# BRG_Daughter_Single.net
KiCad netlist of a schematic drawn in Altium Designer
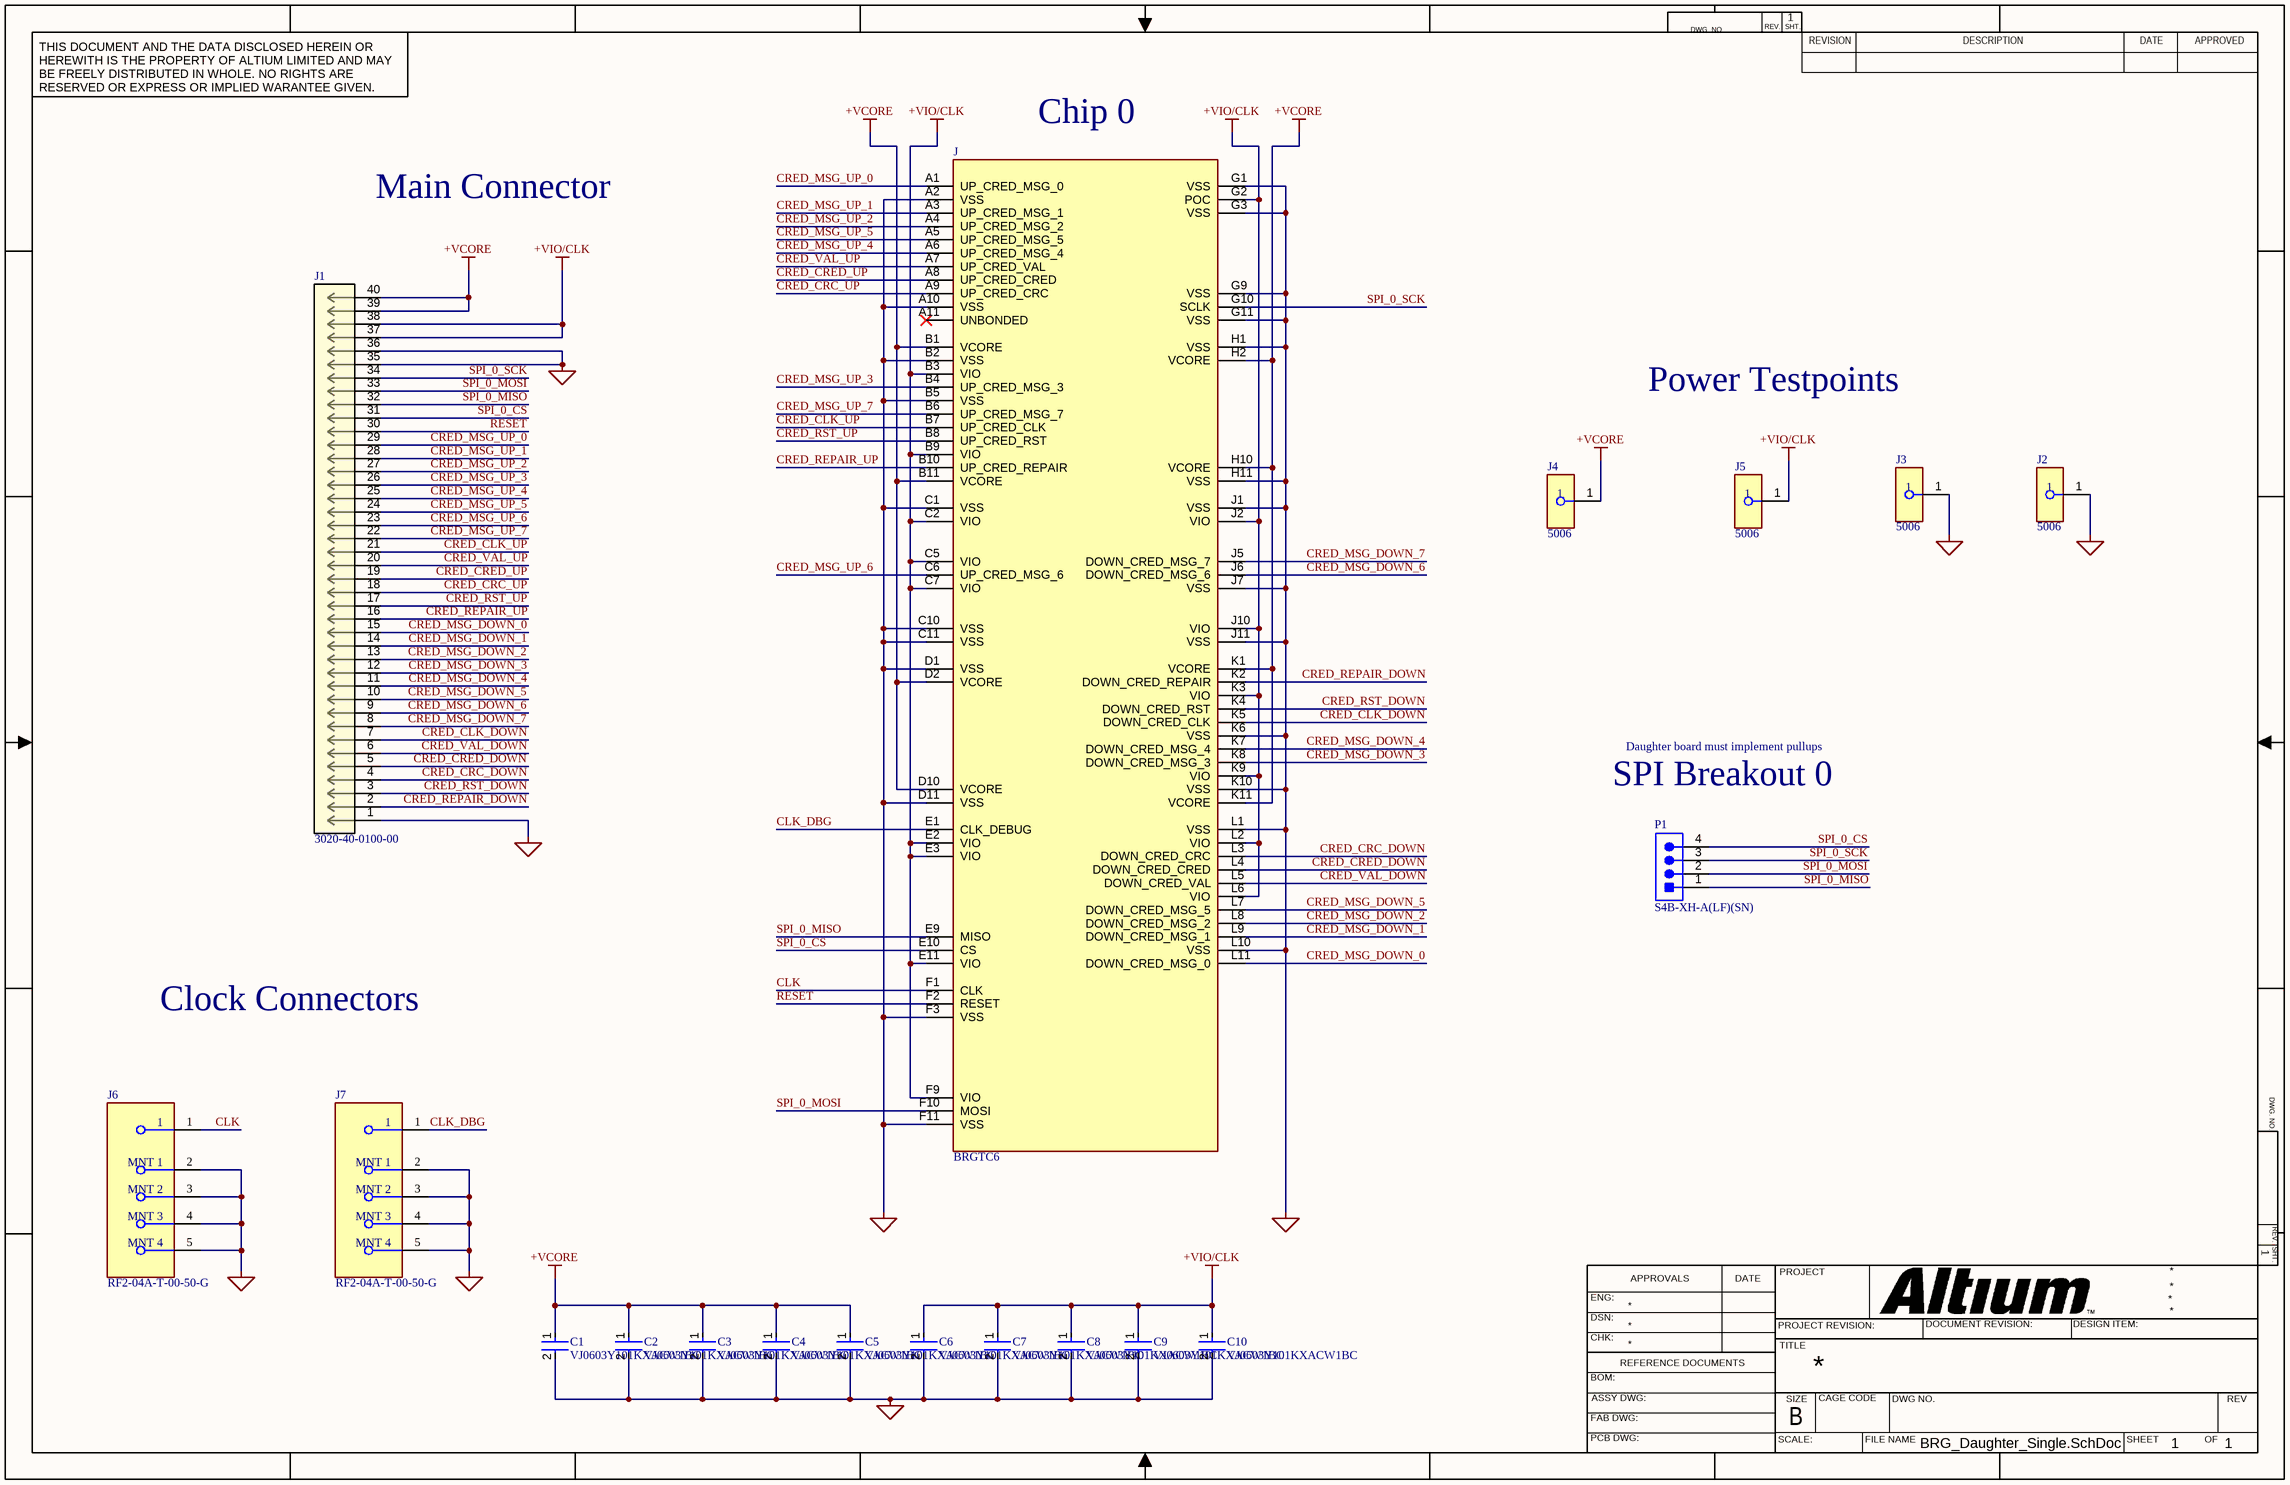
[diagram p0: BRG_Daughter_Single.SchDoc]

(export (version "E")
  (design (tool "Eeschema 10.0.6"))
  (components
    (comp (ref "C1")
      (value "VJ0603Y101KXACW1BC")
      (footprint "FP-CC0603-DA-MFG")
      (description "CAP CER 0.1UF 16V X7R 0603")
      (fields
        (field (name "OCTOPART") "https://octopart.com/cc0603krx7r7bb104-yageo-192941")
        (field (name "TOLERANCE") "0.1")
      )
      (libsource (lib "Altium Content Vault") (part "11868f565c42a9108669ba33697ecf6"))
    )
    (comp (ref "C2")
      (value "VJ0603Y101KXACW1BC")
      (footprint "FP-CC0603-DA-MFG")
      (description "CAP CER 0.1UF 16V X7R 0603")
      (fields
        (field (name "OCTOPART") "https://octopart.com/cc0603krx7r7bb104-yageo-192941")
        (field (name "TOLERANCE") "0.1")
      )
      (libsource (lib "Altium Content Vault") (part "11868f565c42a9108669ba33697ecf6"))
    )
    (comp (ref "C3")
      (value "VJ0603Y101KXACW1BC")
      (footprint "FP-CC0603-DA-MFG")
      (description "CAP CER 0.1UF 16V X7R 0603")
      (fields
        (field (name "OCTOPART") "https://octopart.com/cc0603krx7r7bb104-yageo-192941")
        (field (name "TOLERANCE") "0.1")
      )
      (libsource (lib "Altium Content Vault") (part "11868f565c42a9108669ba33697ecf6"))
    )
    (comp (ref "C4")
      (value "VJ0603Y101KXACW1BC")
      (footprint "FP-CC0603-DA-MFG")
      (description "CAP CER 0.1UF 16V X7R 0603")
      (fields
        (field (name "OCTOPART") "https://octopart.com/cc0603krx7r7bb104-yageo-192941")
        (field (name "TOLERANCE") "0.1")
      )
      (libsource (lib "Altium Content Vault") (part "11868f565c42a9108669ba33697ecf6"))
    )
    (comp (ref "C5")
      (value "VJ0603Y101KXACW1BC")
      (footprint "FP-CC0603-DA-MFG")
      (description "CAP CER 0.1UF 16V X7R 0603")
      (fields
        (field (name "OCTOPART") "https://octopart.com/cc0603krx7r7bb104-yageo-192941")
        (field (name "TOLERANCE") "0.1")
      )
      (libsource (lib "Altium Content Vault") (part "11868f565c42a9108669ba33697ecf6"))
    )
    (comp (ref "C6")
      (value "VJ0603Y101KXACW1BC")
      (footprint "FP-CC0603-DA-MFG")
      (description "CAP CER 0.1UF 16V X7R 0603")
      (fields
        (field (name "OCTOPART") "https://octopart.com/cc0603krx7r7bb104-yageo-192941")
        (field (name "TOLERANCE") "0.1")
      )
      (libsource (lib "Altium Content Vault") (part "11868f565c42a9108669ba33697ecf6"))
    )
    (comp (ref "C7")
      (value "VJ0603Y101KXACW1BC")
      (footprint "FP-CC0603-DA-MFG")
      (description "CAP CER 0.1UF 16V X7R 0603")
      (fields
        (field (name "OCTOPART") "https://octopart.com/cc0603krx7r7bb104-yageo-192941")
        (field (name "TOLERANCE") "0.1")
      )
      (libsource (lib "Altium Content Vault") (part "11868f565c42a9108669ba33697ecf6"))
    )
    (comp (ref "C8")
      (value "VJ0603Y101KXACW1BC")
      (footprint "FP-CC0603-DA-MFG")
      (description "CAP CER 0.1UF 16V X7R 0603")
      (fields
        (field (name "OCTOPART") "https://octopart.com/cc0603krx7r7bb104-yageo-192941")
        (field (name "TOLERANCE") "0.1")
      )
      (libsource (lib "Altium Content Vault") (part "11868f565c42a9108669ba33697ecf6"))
    )
    (comp (ref "C9")
      (value "VJ0603Y101KXACW1BC")
      (footprint "FP-CC0603-DA-MFG")
      (description "CAP CER 0.1UF 16V X7R 0603")
      (fields
        (field (name "OCTOPART") "https://octopart.com/cc0603krx7r7bb104-yageo-192941")
        (field (name "TOLERANCE") "0.1")
      )
      (libsource (lib "Altium Content Vault") (part "11868f565c42a9108669ba33697ecf6"))
    )
    (comp (ref "C10")
      (value "VJ0603Y101KXACW1BC")
      (footprint "FP-CC0603-DA-MFG")
      (description "CAP CER 0.1UF 16V X7R 0603")
      (fields
        (field (name "OCTOPART") "https://octopart.com/cc0603krx7r7bb104-yageo-192941")
        (field (name "TOLERANCE") "0.1")
      )
      (libsource (lib "Altium Content Vault") (part "11868f565c42a9108669ba33697ecf6"))
    )
    (comp (ref "J")
      (value "BRGTC6")
      (footprint "3M_200-6311-9UN-1900")
      (description "121 _11 x 11_ Pos PGA, ZIF _ZIP_ Socket Gold Through Hole")
      (fields (field (name "DIGI-KEY_PART_NUMBER") "3M5067-ND") (field (name "MF") "3M"))
      (libsource (lib "BRGTC6") (part "200-6311-9UN-1900"))
    )
    (comp (ref "J1")
      (value "3020-40-0100-00")
      (footprint "CONN_3020-40-0100-00_CNC")
      (description "No Description Available")
      (libsource (lib "3020-40-0100-00") (part "3020-40-0100-00"))
    )
    (comp (ref "J2")
      (value "5006")
      (footprint "FP-5006-MFG")
      (description "PC TEST POINT COMPACT BLACK")
      (libsource (lib "Altium Content Vault") (part "98815daf2f2c152b0c43f5ab9800df6"))
    )
    (comp (ref "J3")
      (value "5006")
      (footprint "FP-5006-MFG")
      (description "PC TEST POINT COMPACT BLACK")
      (libsource (lib "Altium Content Vault") (part "98815daf2f2c152b0c43f5ab9800df6"))
    )
    (comp (ref "J4")
      (value "5006")
      (footprint "FP-5006-MFG")
      (description "PC TEST POINT COMPACT BLACK")
      (libsource (lib "Altium Content Vault") (part "98815daf2f2c152b0c43f5ab9800df6"))
    )
    (comp (ref "J5")
      (value "5006")
      (footprint "FP-5006-MFG")
      (description "PC TEST POINT COMPACT BLACK")
      (libsource (lib "Altium Content Vault") (part "98815daf2f2c152b0c43f5ab9800df6"))
    )
    (comp (ref "J6")
      (value "RF2-04A-T-00-50-G")
      (footprint "FP-RF2-04A-T-00-50-G-MFG")
      (description "CONN SMA JACK STR 50 OHM PCB")
      (libsource (lib "Altium Content Vault") (part "c65b8a639cdaef1819ea20b5466f8fa"))
    )
    (comp (ref "J7")
      (value "RF2-04A-T-00-50-G")
      (footprint "FP-RF2-04A-T-00-50-G-MFG")
      (description "CONN SMA JACK STR 50 OHM PCB")
      (libsource (lib "Altium Content Vault") (part "c65b8a639cdaef1819ea20b5466f8fa"))
    )
    (comp (ref "P1")
      (value "S4B-XH-A(LF)(SN)")
      (footprint "JST-S4B-XH-A(LF)(SN)_V")
      (libsource (lib "Altium Content Vault") (part "CN-1P-M-R4"))
    )
  )
  (nets
    (net (code "1") (name "+VCORE") (class "Default")
      (node (ref "C1") (pin "1") (pinfunction "1_1") (pintype "passive"))
      (node (ref "C2") (pin "1") (pinfunction "1_1") (pintype "passive"))
      (node (ref "C3") (pin "1") (pinfunction "1_1") (pintype "passive"))
      (node (ref "C4") (pin "1") (pinfunction "1_1") (pintype "passive"))
      (node (ref "C5") (pin "1") (pinfunction "1_1") (pintype "passive"))
      (node (ref "J") (pin "B1") (pinfunction "VCORE_B1") (pintype "passive"))
      (node (ref "J") (pin "B11") (pinfunction "VCORE_B11") (pintype "passive"))
      (node (ref "J") (pin "D10") (pinfunction "VCORE_D10") (pintype "passive"))
      (node (ref "J") (pin "D2") (pinfunction "VCORE_D2") (pintype "passive"))
      (node (ref "J") (pin "H10") (pinfunction "VCORE_H10") (pintype "passive"))
      (node (ref "J") (pin "H2") (pinfunction "VCORE_H2") (pintype "passive"))
      (node (ref "J") (pin "K1") (pinfunction "VCORE_K1") (pintype "passive"))
      (node (ref "J") (pin "K11") (pinfunction "VCORE_K11") (pintype "passive"))
      (node (ref "J1") (pin "39") (pinfunction "39_39") (pintype "passive"))
      (node (ref "J1") (pin "40") (pinfunction "40_40") (pintype "passive"))
      (node (ref "J4") (pin "1") (pinfunction "1_1") (pintype "passive"))
    )
    (net (code "2") (name "+VIO{slash}CLK") (class "Default")
      (node (ref "C10") (pin "1") (pinfunction "1_1") (pintype "passive"))
      (node (ref "C6") (pin "1") (pinfunction "1_1") (pintype "passive"))
      (node (ref "C7") (pin "1") (pinfunction "1_1") (pintype "passive"))
      (node (ref "C8") (pin "1") (pinfunction "1_1") (pintype "passive"))
      (node (ref "C9") (pin "1") (pinfunction "1_1") (pintype "passive"))
      (node (ref "J") (pin "B3") (pinfunction "VIO_B3") (pintype "passive"))
      (node (ref "J") (pin "B9") (pinfunction "VIO_B9") (pintype "passive"))
      (node (ref "J") (pin "C2") (pinfunction "VIO_C2") (pintype "passive"))
      (node (ref "J") (pin "C5") (pinfunction "VIO_C5") (pintype "passive"))
      (node (ref "J") (pin "C7") (pinfunction "VIO_C7") (pintype "passive"))
      (node (ref "J") (pin "E11") (pinfunction "VIO_E11") (pintype "passive"))
      (node (ref "J") (pin "E2") (pinfunction "VIO_E2") (pintype "passive"))
      (node (ref "J") (pin "E3") (pinfunction "VIO_E3") (pintype "passive"))
      (node (ref "J") (pin "F9") (pinfunction "VIO_F9") (pintype "passive"))
      (node (ref "J") (pin "G2") (pinfunction "POC_G2") (pintype "passive"))
      (node (ref "J") (pin "J10") (pinfunction "VIO_J10") (pintype "passive"))
      (node (ref "J") (pin "J2") (pinfunction "VIO_J2") (pintype "passive"))
      (node (ref "J") (pin "K3") (pinfunction "VIO_K3") (pintype "passive"))
      (node (ref "J") (pin "K9") (pinfunction "VIO_K9") (pintype "passive"))
      (node (ref "J") (pin "L2") (pinfunction "VIO_L2") (pintype "passive"))
      (node (ref "J") (pin "L6") (pinfunction "VIO_L6") (pintype "passive"))
      (node (ref "J1") (pin "37") (pinfunction "37_37") (pintype "passive"))
      (node (ref "J1") (pin "38") (pinfunction "38_38") (pintype "passive"))
      (node (ref "J5") (pin "1") (pinfunction "1_1") (pintype "passive"))
    )
    (net (code "3") (name "/CLK") (class "Default")
      (node (ref "J") (pin "F1") (pinfunction "CLK_F1") (pintype "passive"))
      (node (ref "J6") (pin "1") (pinfunction "1_1") (pintype "passive"))
    )
    (net (code "4") (name "/CLK_DBG") (class "Default")
      (node (ref "J") (pin "E1") (pinfunction "CLK_DEBUG_E1") (pintype "passive"))
      (node (ref "J7") (pin "1") (pinfunction "1_1") (pintype "passive"))
    )
    (net (code "5") (name "/CRED_CLK_DOWN") (class "Default")
      (node (ref "J") (pin "K5") (pinfunction "DOWN_CRED_CLK_K5") (pintype "passive"))
      (node (ref "J1") (pin "7") (pinfunction "7_7") (pintype "passive"))
    )
    (net (code "6") (name "/CRED_CLK_UP") (class "Default")
      (node (ref "J") (pin "B7") (pinfunction "UP_CRED_CLK_B7") (pintype "passive"))
      (node (ref "J1") (pin "21") (pinfunction "21_21") (pintype "passive"))
    )
    (net (code "7") (name "/CRED_CRC_DOWN") (class "Default")
      (node (ref "J") (pin "L3") (pinfunction "DOWN_CRED_CRC_L3") (pintype "passive"))
      (node (ref "J1") (pin "4") (pinfunction "4_4") (pintype "passive"))
    )
    (net (code "8") (name "/CRED_CRC_UP") (class "Default")
      (node (ref "J") (pin "A9") (pinfunction "UP_CRED_CRC_A9") (pintype "passive"))
      (node (ref "J1") (pin "18") (pinfunction "18_18") (pintype "passive"))
    )
    (net (code "9") (name "/CRED_CRED_DOWN") (class "Default")
      (node (ref "J") (pin "L4") (pinfunction "DOWN_CRED_CRED_L4") (pintype "passive"))
      (node (ref "J1") (pin "5") (pinfunction "5_5") (pintype "passive"))
    )
    (net (code "10") (name "/CRED_CRED_UP") (class "Default")
      (node (ref "J") (pin "A8") (pinfunction "UP_CRED_CRED_A8") (pintype "passive"))
      (node (ref "J1") (pin "19") (pinfunction "19_19") (pintype "passive"))
    )
    (net (code "11") (name "/CRED_MSG_DOWN_0") (class "Default")
      (node (ref "J") (pin "L11") (pinfunction "DOWN_CRED_MSG_0_L11") (pintype "passive"))
      (node (ref "J1") (pin "15") (pinfunction "15_15") (pintype "passive"))
    )
    (net (code "12") (name "/CRED_MSG_DOWN_1") (class "Default")
      (node (ref "J") (pin "L9") (pinfunction "DOWN_CRED_MSG_1_L9") (pintype "passive"))
      (node (ref "J1") (pin "14") (pinfunction "14_14") (pintype "passive"))
    )
    (net (code "13") (name "/CRED_MSG_DOWN_2") (class "Default")
      (node (ref "J") (pin "L8") (pinfunction "DOWN_CRED_MSG_2_L8") (pintype "passive"))
      (node (ref "J1") (pin "13") (pinfunction "13_13") (pintype "passive"))
    )
    (net (code "14") (name "/CRED_MSG_DOWN_3") (class "Default")
      (node (ref "J") (pin "K8") (pinfunction "DOWN_CRED_MSG_3_K8") (pintype "passive"))
      (node (ref "J1") (pin "12") (pinfunction "12_12") (pintype "passive"))
    )
    (net (code "15") (name "/CRED_MSG_DOWN_4") (class "Default")
      (node (ref "J") (pin "K7") (pinfunction "DOWN_CRED_MSG_4_K7") (pintype "passive"))
      (node (ref "J1") (pin "11") (pinfunction "11_11") (pintype "passive"))
    )
    (net (code "16") (name "/CRED_MSG_DOWN_5") (class "Default")
      (node (ref "J") (pin "L7") (pinfunction "DOWN_CRED_MSG_5_L7") (pintype "passive"))
      (node (ref "J1") (pin "10") (pinfunction "10_10") (pintype "passive"))
    )
    (net (code "17") (name "/CRED_MSG_DOWN_6") (class "Default")
      (node (ref "J") (pin "J6") (pinfunction "DOWN_CRED_MSG_6_J6") (pintype "passive"))
      (node (ref "J1") (pin "9") (pinfunction "9_9") (pintype "passive"))
    )
    (net (code "18") (name "/CRED_MSG_DOWN_7") (class "Default")
      (node (ref "J") (pin "J5") (pinfunction "DOWN_CRED_MSG_7_J5") (pintype "passive"))
      (node (ref "J1") (pin "8") (pinfunction "8_8") (pintype "passive"))
    )
    (net (code "19") (name "/CRED_MSG_UP_0") (class "Default")
      (node (ref "J") (pin "A1") (pinfunction "UP_CRED_MSG_0_A1") (pintype "passive"))
      (node (ref "J1") (pin "29") (pinfunction "29_29") (pintype "passive"))
    )
    (net (code "20") (name "/CRED_MSG_UP_1") (class "Default")
      (node (ref "J") (pin "A3") (pinfunction "UP_CRED_MSG_1_A3") (pintype "passive"))
      (node (ref "J1") (pin "28") (pinfunction "28_28") (pintype "passive"))
    )
    (net (code "21") (name "/CRED_MSG_UP_2") (class "Default")
      (node (ref "J") (pin "A4") (pinfunction "UP_CRED_MSG_2_A4") (pintype "passive"))
      (node (ref "J1") (pin "27") (pinfunction "27_27") (pintype "passive"))
    )
    (net (code "22") (name "/CRED_MSG_UP_3") (class "Default")
      (node (ref "J") (pin "B4") (pinfunction "UP_CRED_MSG_3_B4") (pintype "passive"))
      (node (ref "J1") (pin "26") (pinfunction "26_26") (pintype "passive"))
    )
    (net (code "23") (name "/CRED_MSG_UP_4") (class "Default")
      (node (ref "J") (pin "A6") (pinfunction "UP_CRED_MSG_4_A6") (pintype "passive"))
      (node (ref "J1") (pin "25") (pinfunction "25_25") (pintype "passive"))
    )
    (net (code "24") (name "/CRED_MSG_UP_5") (class "Default")
      (node (ref "J") (pin "A5") (pinfunction "UP_CRED_MSG_5_A5") (pintype "passive"))
      (node (ref "J1") (pin "24") (pinfunction "24_24") (pintype "passive"))
    )
    (net (code "25") (name "/CRED_MSG_UP_6") (class "Default")
      (node (ref "J") (pin "C6") (pinfunction "UP_CRED_MSG_6_C6") (pintype "passive"))
      (node (ref "J1") (pin "23") (pinfunction "23_23") (pintype "passive"))
    )
    (net (code "26") (name "/CRED_MSG_UP_7") (class "Default")
      (node (ref "J") (pin "B6") (pinfunction "UP_CRED_MSG_7_B6") (pintype "passive"))
      (node (ref "J1") (pin "22") (pinfunction "22_22") (pintype "passive"))
    )
    (net (code "27") (name "/CRED_REPAIR_DOWN") (class "Default")
      (node (ref "J") (pin "K2") (pinfunction "DOWN_CRED_REPAIR_K2") (pintype "passive"))
      (node (ref "J1") (pin "2") (pinfunction "2_2") (pintype "passive"))
    )
    (net (code "28") (name "/CRED_REPAIR_UP") (class "Default")
      (node (ref "J") (pin "B10") (pinfunction "UP_CRED_REPAIR_B10") (pintype "passive"))
      (node (ref "J1") (pin "16") (pinfunction "16_16") (pintype "passive"))
    )
    (net (code "29") (name "/CRED_RST_DOWN") (class "Default")
      (node (ref "J") (pin "K4") (pinfunction "DOWN_CRED_RST_K4") (pintype "passive"))
      (node (ref "J1") (pin "3") (pinfunction "3_3") (pintype "passive"))
    )
    (net (code "30") (name "/CRED_RST_UP") (class "Default")
      (node (ref "J") (pin "B8") (pinfunction "UP_CRED_RST_B8") (pintype "passive"))
      (node (ref "J1") (pin "17") (pinfunction "17_17") (pintype "passive"))
    )
    (net (code "31") (name "/CRED_VAL_DOWN") (class "Default")
      (node (ref "J") (pin "L5") (pinfunction "DOWN_CRED_VAL_L5") (pintype "passive"))
      (node (ref "J1") (pin "6") (pinfunction "6_6") (pintype "passive"))
    )
    (net (code "32") (name "/CRED_VAL_UP") (class "Default")
      (node (ref "J") (pin "A7") (pinfunction "UP_CRED_VAL_A7") (pintype "passive"))
      (node (ref "J1") (pin "20") (pinfunction "20_20") (pintype "passive"))
    )
    (net (code "33") (name "/RESET") (class "Default")
      (node (ref "J") (pin "F2") (pinfunction "RESET_F2") (pintype "passive"))
      (node (ref "J1") (pin "30") (pinfunction "30_30") (pintype "passive"))
    )
    (net (code "34") (name "/SPI_0_CS") (class "Default")
      (node (ref "J") (pin "E10") (pinfunction "CS_E10") (pintype "passive"))
      (node (ref "J1") (pin "31") (pinfunction "31_31") (pintype "passive"))
      (node (ref "P1") (pin "4") (pinfunction "4_4") (pintype "passive"))
    )
    (net (code "35") (name "/SPI_0_MISO") (class "Default")
      (node (ref "J") (pin "E9") (pinfunction "MISO_E9") (pintype "passive"))
      (node (ref "J1") (pin "32") (pinfunction "32_32") (pintype "passive"))
      (node (ref "P1") (pin "1") (pinfunction "1_1") (pintype "passive"))
    )
    (net (code "36") (name "/SPI_0_MOSI") (class "Default")
      (node (ref "J") (pin "F10") (pinfunction "MOSI_F10") (pintype "passive"))
      (node (ref "J1") (pin "33") (pinfunction "33_33") (pintype "passive"))
      (node (ref "P1") (pin "2") (pinfunction "2_2") (pintype "passive"))
    )
    (net (code "37") (name "/SPI_0_SCK") (class "Default")
      (node (ref "J") (pin "G10") (pinfunction "SCLK_G10") (pintype "passive"))
      (node (ref "J1") (pin "34") (pinfunction "34_34") (pintype "passive"))
      (node (ref "P1") (pin "3") (pinfunction "3_3") (pintype "passive"))
    )
    (net (code "38") (name "GND") (class "Default")
      (node (ref "C1") (pin "2") (pinfunction "2_2") (pintype "passive"))
      (node (ref "C10") (pin "2") (pinfunction "2_2") (pintype "passive"))
      (node (ref "C2") (pin "2") (pinfunction "2_2") (pintype "passive"))
      (node (ref "C3") (pin "2") (pinfunction "2_2") (pintype "passive"))
      (node (ref "C4") (pin "2") (pinfunction "2_2") (pintype "passive"))
      (node (ref "C5") (pin "2") (pinfunction "2_2") (pintype "passive"))
      (node (ref "C6") (pin "2") (pinfunction "2_2") (pintype "passive"))
      (node (ref "C7") (pin "2") (pinfunction "2_2") (pintype "passive"))
      (node (ref "C8") (pin "2") (pinfunction "2_2") (pintype "passive"))
      (node (ref "C9") (pin "2") (pinfunction "2_2") (pintype "passive"))
      (node (ref "J") (pin "A10") (pinfunction "VSS_A10") (pintype "passive"))
      (node (ref "J") (pin "A2") (pinfunction "VSS_A2") (pintype "passive"))
      (node (ref "J") (pin "B2") (pinfunction "VSS_B2") (pintype "passive"))
      (node (ref "J") (pin "B5") (pinfunction "VSS_B5") (pintype "passive"))
      (node (ref "J") (pin "C1") (pinfunction "VSS_C1") (pintype "passive"))
      (node (ref "J") (pin "C10") (pinfunction "VSS_C10") (pintype "passive"))
      (node (ref "J") (pin "C11") (pinfunction "VSS_C11") (pintype "passive"))
      (node (ref "J") (pin "D1") (pinfunction "VSS_D1") (pintype "passive"))
      (node (ref "J") (pin "D11") (pinfunction "VSS_D11") (pintype "passive"))
      (node (ref "J") (pin "F11") (pinfunction "VSS_F11") (pintype "passive"))
      (node (ref "J") (pin "F3") (pinfunction "VSS_F3") (pintype "passive"))
      (node (ref "J") (pin "G1") (pinfunction "VSS_G1") (pintype "passive"))
      (node (ref "J") (pin "G11") (pinfunction "VSS_G11") (pintype "passive"))
      (node (ref "J") (pin "G3") (pinfunction "VSS_G3") (pintype "passive"))
      (node (ref "J") (pin "G9") (pinfunction "VSS_G9") (pintype "passive"))
      (node (ref "J") (pin "H1") (pinfunction "VSS_H1") (pintype "passive"))
      (node (ref "J") (pin "H11") (pinfunction "VSS_H11") (pintype "passive"))
      (node (ref "J") (pin "J1") (pinfunction "VSS_J1") (pintype "passive"))
      (node (ref "J") (pin "J11") (pinfunction "VSS_J11") (pintype "passive"))
      (node (ref "J") (pin "J7") (pinfunction "VSS_J7") (pintype "passive"))
      (node (ref "J") (pin "K10") (pinfunction "VSS_K10") (pintype "passive"))
      (node (ref "J") (pin "K6") (pinfunction "VSS_K6") (pintype "passive"))
      (node (ref "J") (pin "L1") (pinfunction "VSS_L1") (pintype "passive"))
      (node (ref "J") (pin "L10") (pinfunction "VSS_L10") (pintype "passive"))
      (node (ref "J1") (pin "1") (pinfunction "1_1") (pintype "passive"))
      (node (ref "J1") (pin "35") (pinfunction "35_35") (pintype "passive"))
      (node (ref "J1") (pin "36") (pinfunction "36_36") (pintype "passive"))
      (node (ref "J2") (pin "1") (pinfunction "1_1") (pintype "passive"))
      (node (ref "J3") (pin "1") (pinfunction "1_1") (pintype "passive"))
      (node (ref "J6") (pin "2") (pinfunction "MNT_1_2") (pintype "passive"))
      (node (ref "J6") (pin "3") (pinfunction "MNT_2_3") (pintype "passive"))
      (node (ref "J6") (pin "4") (pinfunction "MNT_3_4") (pintype "passive"))
      (node (ref "J6") (pin "5") (pinfunction "MNT_4_5") (pintype "passive"))
      (node (ref "J7") (pin "2") (pinfunction "MNT_1_2") (pintype "passive"))
      (node (ref "J7") (pin "3") (pinfunction "MNT_2_3") (pintype "passive"))
      (node (ref "J7") (pin "4") (pinfunction "MNT_3_4") (pintype "passive"))
      (node (ref "J7") (pin "5") (pinfunction "MNT_4_5") (pintype "passive"))
    )
    (net (code "39") (name "unconnected-(J-UNBONDED-PadA11)") (class "Default")
      (node (ref "J") (pin "A11") (pinfunction "UNBONDED_A11") (pintype "passive+no_connect"))
    )
  )
)
